# buck_converter.net
KiCad netlist of a schematic drawn in EAGLE
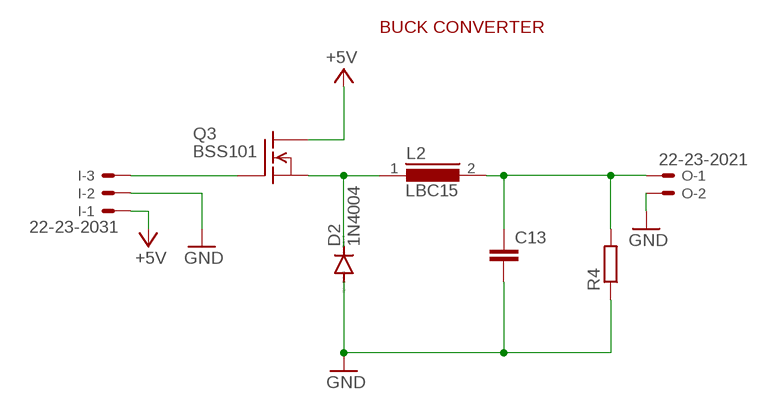
[diagram p0: schematic, sheet 1]

(export (version "E")
  (design (tool "Eeschema 10.0.6"))
  (components
    (comp (ref "C13")
      (value "C2.5/2")
      (footprint "eagle-import:C2.5-2")
      (libsource (lib "eagle-import") (part "C2.5/2"))
    )
    (comp (ref "D2")
      (value "1N4004")
      (footprint "eagle-import:DO41-10")
      (libsource (lib "eagle-import") (part "1N4004"))
    )
    (comp (ref "I")
      (value "22-23-2031")
      (footprint "eagle-import:22-23-2031")
      (fields (field (name "MF") "MOLEX"))
      (libsource (lib "eagle-import") (part "22-23-2031"))
    )
    (comp (ref "L2")
      (value "LBC15")
      (footprint "eagle-import:LBC15")
      (libsource (lib "eagle-import") (part "LBC15"))
    )
    (comp (ref "O")
      (value "22-23-2021")
      (footprint "eagle-import:22-23-2021")
      (fields (field (name "MF") "MOLEX"))
      (libsource (lib "eagle-import") (part "22-23-2021"))
    )
    (comp (ref "Q3")
      (value "BSS101")
      (footprint "eagle-import:TO92")
      (libsource (lib "eagle-import") (part "BSS101"))
    )
    (comp (ref "R4")
      (value "R-EU_0207/10")
      (footprint "eagle-import:0207_10")
      (libsource (lib "eagle-import") (part "R-EU_0207/10"))
    )
  )
  (nets
    (net (code "1") (name "+5V") (class "Default")
      (node (ref "I") (pin "1") (pinfunction "S_1") (pintype "passive"))
      (node (ref "Q3") (pin "3") (pinfunction "D_3") (pintype "passive"))
    )
    (net (code "2") (name "GND") (class "Default")
      (node (ref "C13") (pin "2") (pinfunction "2_2") (pintype "passive"))
      (node (ref "D2") (pin "A") (pinfunction "A_A") (pintype "passive"))
      (node (ref "I") (pin "2") (pinfunction "S_2") (pintype "passive"))
      (node (ref "O") (pin "2") (pinfunction "S_2") (pintype "passive"))
      (node (ref "R4") (pin "1") (pinfunction "1_1") (pintype "passive"))
    )
    (net (code "3") (name "Net-(IC-S)") (class "Default")
      (node (ref "I") (pin "3") (pinfunction "S_3") (pintype "passive"))
      (node (ref "Q3") (pin "2") (pinfunction "G_2") (pintype "passive"))
    )
    (net (code "4") (name "Net-(OA-S)") (class "Default")
      (node (ref "C13") (pin "1") (pinfunction "1_1") (pintype "passive"))
      (node (ref "L2") (pin "2") (pinfunction "2_2") (pintype "passive"))
      (node (ref "O") (pin "1") (pinfunction "S_1") (pintype "passive"))
      (node (ref "R4") (pin "2") (pinfunction "2_2") (pintype "passive"))
    )
    (net (code "5") (name "Net-(Q3-S)") (class "Default")
      (node (ref "D2") (pin "C") (pinfunction "C_C") (pintype "passive"))
      (node (ref "L2") (pin "1") (pinfunction "1_1") (pintype "passive"))
      (node (ref "Q3") (pin "1") (pinfunction "S_1") (pintype "passive"))
    )
  )
)
